# ESP32_Connection.net
KiCad netlist of a schematic drawn in Altium Designer
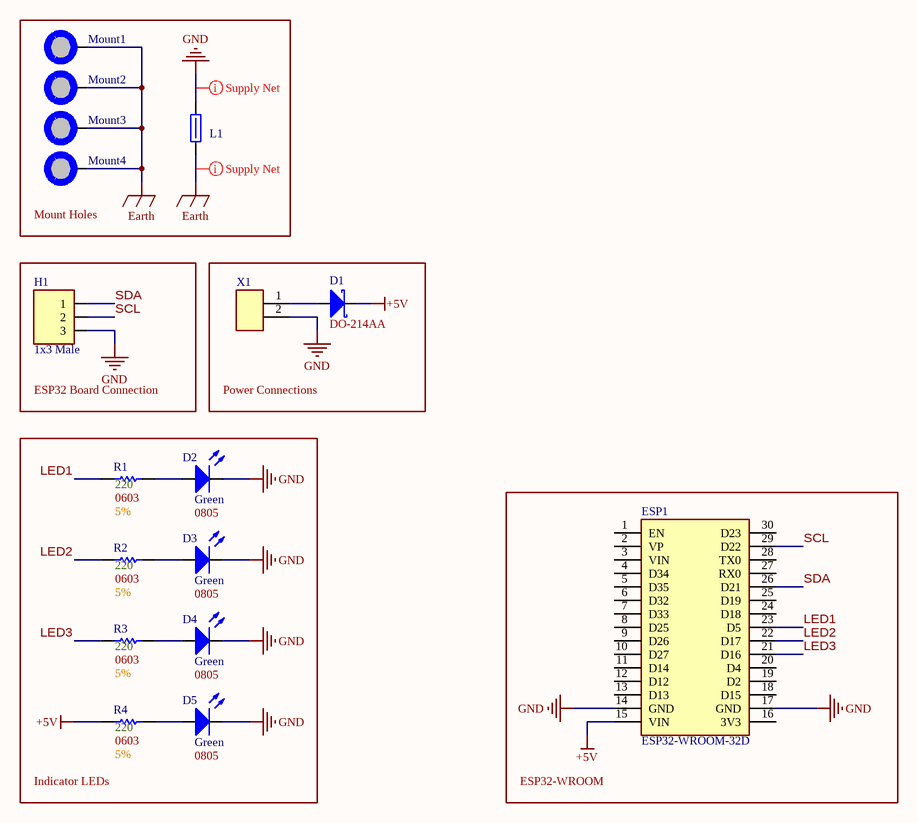
[diagram p0: ESP32 Connection.SchDoc]

(export (version "E")
  (design (tool "Eeschema 10.0.6"))
  (components
    (comp (ref "D1")
      (value "Schottky")
      (footprint "[Diode] SMD DO-214AA")
      (description "Generic")
      (fields (field (name "SIZE PACKAGE") "DO-214AA"))
      (libsource (lib "RADM Components") (part "[Diode] SMD Schottky"))
    )
    (comp (ref "D2")
      (value "SMD LED")
      (footprint "[LED] SMD 0805")
      (description "Generic")
      (fields (field (name "COLOR") "Green") (field (name "SIZE PACKAGE") "0805"))
      (libsource (lib "RADM Components") (part "[LED] SMD"))
    )
    (comp (ref "D3")
      (value "SMD LED")
      (footprint "[LED] SMD 0805")
      (description "Generic")
      (fields (field (name "COLOR") "Green") (field (name "SIZE PACKAGE") "0805"))
      (libsource (lib "RADM Components") (part "[LED] SMD"))
    )
    (comp (ref "D4")
      (value "SMD LED")
      (footprint "[LED] SMD 0805")
      (description "Generic")
      (fields (field (name "COLOR") "Green") (field (name "SIZE PACKAGE") "0805"))
      (libsource (lib "RADM Components") (part "[LED] SMD"))
    )
    (comp (ref "D5")
      (value "SMD LED")
      (footprint "[LED] SMD 0805")
      (description "Generic")
      (fields (field (name "COLOR") "Green") (field (name "SIZE PACKAGE") "0805"))
      (libsource (lib "RADM Components") (part "[LED] SMD"))
    )
    (comp (ref "ESP1")
      (value "ESP32-WROOM-32D")
      (footprint "[Device] ESP32-WROOM-32D")
      (description "ESP32 DEVKIT V1 - DOIT")
      (libsource (lib "RADM Components") (part "[Device] ESP32-WROOM-32D"))
    )
    (comp (ref "H1")
      (value "1x3 Male")
      (footprint "[Header] Shrouded 1x3 Male")
      (description "070543-0037\r\nMates with 005057-9403")
      (libsource (lib "RADM Connectors") (part "[Header] Shrouded 1x3 Male"))
    )
    (comp (ref "L1")
      (value "652-MH2029-300Y")
      (footprint "[Ferrite] SMD Bead 0805 (1)")
      (libsource (lib "RADM Components") (part "[Ferrite] SMD Ferrite Bead (1)"))
    )
    (comp (ref "Mount1")
      (value "M3 Mount Hole")
      (footprint "[Mount] M3 Mount Hole")
      (description "Place at least 4.5mm from board edge. Plated.")
      (libsource (lib "RADM Connectors") (part "[Mount] M3 Mount Hole"))
    )
    (comp (ref "Mount2")
      (value "M3 Mount Hole")
      (footprint "[Mount] M3 Mount Hole")
      (description "Place at least 4.5mm from board edge. Plated.")
      (libsource (lib "RADM Connectors") (part "[Mount] M3 Mount Hole"))
    )
    (comp (ref "Mount3")
      (value "M3 Mount Hole")
      (footprint "[Mount] M3 Mount Hole")
      (description "Place at least 4.5mm from board edge. Plated.")
      (libsource (lib "RADM Connectors") (part "[Mount] M3 Mount Hole"))
    )
    (comp (ref "Mount4")
      (value "M3 Mount Hole")
      (footprint "[Mount] M3 Mount Hole")
      (description "Place at least 4.5mm from board edge. Plated.")
      (libsource (lib "RADM Connectors") (part "[Mount] M3 Mount Hole"))
    )
    (comp (ref "R1")
      (value "[Res] SMD Resistor")
      (footprint "[Res] SMD 0603")
      (description "Generic")
      (fields
        (field (name "RESISTANCE") "220")
        (field (name "SIZE PACKAGE") "0603")
        (field (name "TOLERANCE") "5%")
      )
      (libsource (lib "RADM Components") (part "[Res] SMD Resistor"))
    )
    (comp (ref "R2")
      (value "[Res] SMD Resistor")
      (footprint "[Res] SMD 0603")
      (description "Generic")
      (fields
        (field (name "RESISTANCE") "220")
        (field (name "SIZE PACKAGE") "0603")
        (field (name "TOLERANCE") "5%")
      )
      (libsource (lib "RADM Components") (part "[Res] SMD Resistor"))
    )
    (comp (ref "R3")
      (value "[Res] SMD Resistor")
      (footprint "[Res] SMD 0603")
      (description "Generic")
      (fields
        (field (name "RESISTANCE") "220")
        (field (name "SIZE PACKAGE") "0603")
        (field (name "TOLERANCE") "5%")
      )
      (libsource (lib "RADM Components") (part "[Res] SMD Resistor"))
    )
    (comp (ref "R4")
      (value "[Res] SMD Resistor")
      (footprint "[Res] SMD 0603")
      (description "Generic")
      (fields
        (field (name "RESISTANCE") "220")
        (field (name "SIZE PACKAGE") "0603")
        (field (name "TOLERANCE") "5%")
      )
      (libsource (lib "RADM Components") (part "[Res] SMD Resistor"))
    )
    (comp (ref "X1")
      (value "2pin Screw Terminal")
      (footprint "[Screw Terminal] 2pin 5mm")
      (libsource (lib "RADM Connectors") (part "[Screw Terminal] 2pin"))
    )
  )
  (nets
    (net (code "1") (name "+5V") (class "Default")
      (node (ref "D1") (pin "1") (pinfunction "K_1") (pintype "power_in"))
      (node (ref "ESP1") (pin "15") (pinfunction "VIN_15") (pintype "passive"))
      (node (ref "R4") (pin "2") (pinfunction "2_2") (pintype "passive"))
    )
    (net (code "2") (name "/LED1") (class "Default")
      (node (ref "ESP1") (pin "23") (pinfunction "D5_23") (pintype "passive"))
      (node (ref "R1") (pin "2") (pinfunction "2_2") (pintype "passive"))
    )
    (net (code "3") (name "/LED2") (class "Default")
      (node (ref "ESP1") (pin "22") (pinfunction "D17_22") (pintype "passive"))
      (node (ref "R2") (pin "2") (pinfunction "2_2") (pintype "passive"))
    )
    (net (code "4") (name "/LED3") (class "Default")
      (node (ref "ESP1") (pin "21") (pinfunction "D16_21") (pintype "passive"))
      (node (ref "R3") (pin "2") (pinfunction "2_2") (pintype "passive"))
    )
    (net (code "5") (name "/SCL") (class "Default")
      (node (ref "ESP1") (pin "29") (pinfunction "D22_29") (pintype "passive"))
      (node (ref "H1") (pin "2") (pinfunction "2_2") (pintype "passive"))
    )
    (net (code "6") (name "/SDA") (class "Default")
      (node (ref "ESP1") (pin "26") (pinfunction "D21_26") (pintype "passive"))
      (node (ref "H1") (pin "1") (pinfunction "1_1") (pintype "passive"))
    )
    (net (code "7") (name "Earth") (class "Default")
      (node (ref "L1") (pin "1") (pinfunction "1_1") (pintype "passive"))
      (node (ref "Mount1") (pin "1") (pintype "power_in"))
      (node (ref "Mount2") (pin "1") (pintype "power_in"))
      (node (ref "Mount3") (pin "1") (pintype "power_in"))
      (node (ref "Mount4") (pin "1") (pintype "power_in"))
    )
    (net (code "8") (name "GND") (class "Default")
      (node (ref "D2") (pin "2") (pinfunction "Cathode_2") (pintype "passive"))
      (node (ref "D3") (pin "2") (pinfunction "Cathode_2") (pintype "passive"))
      (node (ref "D4") (pin "2") (pinfunction "Cathode_2") (pintype "passive"))
      (node (ref "D5") (pin "2") (pinfunction "Cathode_2") (pintype "passive"))
      (node (ref "ESP1") (pin "14") (pinfunction "GND_14") (pintype "passive"))
      (node (ref "ESP1") (pin "17") (pinfunction "GND_17") (pintype "passive"))
      (node (ref "H1") (pin "3") (pinfunction "3_3") (pintype "passive"))
      (node (ref "L1") (pin "2") (pinfunction "2_2") (pintype "passive"))
      (node (ref "X1") (pin "2") (pintype "power_in"))
    )
    (net (code "9") (name "Net-(D1-A)") (class "Default")
      (node (ref "D1") (pin "2") (pinfunction "A_2") (pintype "power_in"))
      (node (ref "X1") (pin "1") (pintype "power_in"))
    )
    (net (code "10") (name "Net-(D2-Anode)") (class "Default")
      (node (ref "D2") (pin "1") (pinfunction "Anode_1") (pintype "passive"))
      (node (ref "R1") (pin "1") (pinfunction "1_1") (pintype "passive"))
    )
    (net (code "11") (name "Net-(D3-Anode)") (class "Default")
      (node (ref "D3") (pin "1") (pinfunction "Anode_1") (pintype "passive"))
      (node (ref "R2") (pin "1") (pinfunction "1_1") (pintype "passive"))
    )
    (net (code "12") (name "Net-(D4-Anode)") (class "Default")
      (node (ref "D4") (pin "1") (pinfunction "Anode_1") (pintype "passive"))
      (node (ref "R3") (pin "1") (pinfunction "1_1") (pintype "passive"))
    )
    (net (code "13") (name "Net-(D5-Anode)") (class "Default")
      (node (ref "D5") (pin "1") (pinfunction "Anode_1") (pintype "passive"))
      (node (ref "R4") (pin "1") (pinfunction "1_1") (pintype "passive"))
    )
    (net (code "14") (name "unconnected-(ESP1-3V3-Pad16)") (class "Default")
      (node (ref "ESP1") (pin "16") (pinfunction "3V3_16") (pintype "passive"))
    )
    (net (code "15") (name "unconnected-(ESP1-D2-Pad19)") (class "Default")
      (node (ref "ESP1") (pin "19") (pinfunction "D2_19") (pintype "passive"))
    )
    (net (code "16") (name "unconnected-(ESP1-D4-Pad20)") (class "Default")
      (node (ref "ESP1") (pin "20") (pinfunction "D4_20") (pintype "passive"))
    )
    (net (code "17") (name "unconnected-(ESP1-D12-Pad12)") (class "Default")
      (node (ref "ESP1") (pin "12") (pinfunction "D12_12") (pintype "passive"))
    )
    (net (code "18") (name "unconnected-(ESP1-D13-Pad13)") (class "Default")
      (node (ref "ESP1") (pin "13") (pinfunction "D13_13") (pintype "passive"))
    )
    (net (code "19") (name "unconnected-(ESP1-D14-Pad11)") (class "Default")
      (node (ref "ESP1") (pin "11") (pinfunction "D14_11") (pintype "passive"))
    )
    (net (code "20") (name "unconnected-(ESP1-D15-Pad18)") (class "Default")
      (node (ref "ESP1") (pin "18") (pinfunction "D15_18") (pintype "passive"))
    )
    (net (code "21") (name "unconnected-(ESP1-D18-Pad24)") (class "Default")
      (node (ref "ESP1") (pin "24") (pinfunction "D18_24") (pintype "passive"))
    )
    (net (code "22") (name "unconnected-(ESP1-D19-Pad25)") (class "Default")
      (node (ref "ESP1") (pin "25") (pinfunction "D19_25") (pintype "passive"))
    )
    (net (code "23") (name "unconnected-(ESP1-D23-Pad30)") (class "Default")
      (node (ref "ESP1") (pin "30") (pinfunction "D23_30") (pintype "passive"))
    )
    (net (code "24") (name "unconnected-(ESP1-D25-Pad8)") (class "Default")
      (node (ref "ESP1") (pin "8") (pinfunction "D25_8") (pintype "passive"))
    )
    (net (code "25") (name "unconnected-(ESP1-D26-Pad9)") (class "Default")
      (node (ref "ESP1") (pin "9") (pinfunction "D26_9") (pintype "passive"))
    )
    (net (code "26") (name "unconnected-(ESP1-D27-Pad10)") (class "Default")
      (node (ref "ESP1") (pin "10") (pinfunction "D27_10") (pintype "passive"))
    )
    (net (code "27") (name "unconnected-(ESP1-D32-Pad6)") (class "Default")
      (node (ref "ESP1") (pin "6") (pinfunction "D32_6") (pintype "passive"))
    )
    (net (code "28") (name "unconnected-(ESP1-D33-Pad7)") (class "Default")
      (node (ref "ESP1") (pin "7") (pinfunction "D33_7") (pintype "passive"))
    )
    (net (code "29") (name "unconnected-(ESP1-D34-Pad4)") (class "Default")
      (node (ref "ESP1") (pin "4") (pinfunction "D34_4") (pintype "passive"))
    )
    (net (code "30") (name "unconnected-(ESP1-D35-Pad5)") (class "Default")
      (node (ref "ESP1") (pin "5") (pinfunction "D35_5") (pintype "passive"))
    )
    (net (code "31") (name "unconnected-(ESP1-EN-Pad1)") (class "Default")
      (node (ref "ESP1") (pin "1") (pinfunction "EN_1") (pintype "passive"))
    )
    (net (code "32") (name "unconnected-(ESP1-RX0-Pad27)") (class "Default")
      (node (ref "ESP1") (pin "27") (pinfunction "RX0_27") (pintype "passive"))
    )
    (net (code "33") (name "unconnected-(ESP1-TX0-Pad28)") (class "Default")
      (node (ref "ESP1") (pin "28") (pinfunction "TX0_28") (pintype "passive"))
    )
    (net (code "34") (name "unconnected-(ESP1-VIN-Pad3)") (class "Default")
      (node (ref "ESP1") (pin "3") (pinfunction "VIN_3") (pintype "passive"))
    )
    (net (code "35") (name "unconnected-(ESP1-VP-Pad2)") (class "Default")
      (node (ref "ESP1") (pin "2") (pinfunction "VP_2") (pintype "passive"))
    )
  )
)
